# Adafruit_PiTFT_2_4in_HAT.net
KiCad netlist of a schematic drawn in EAGLE
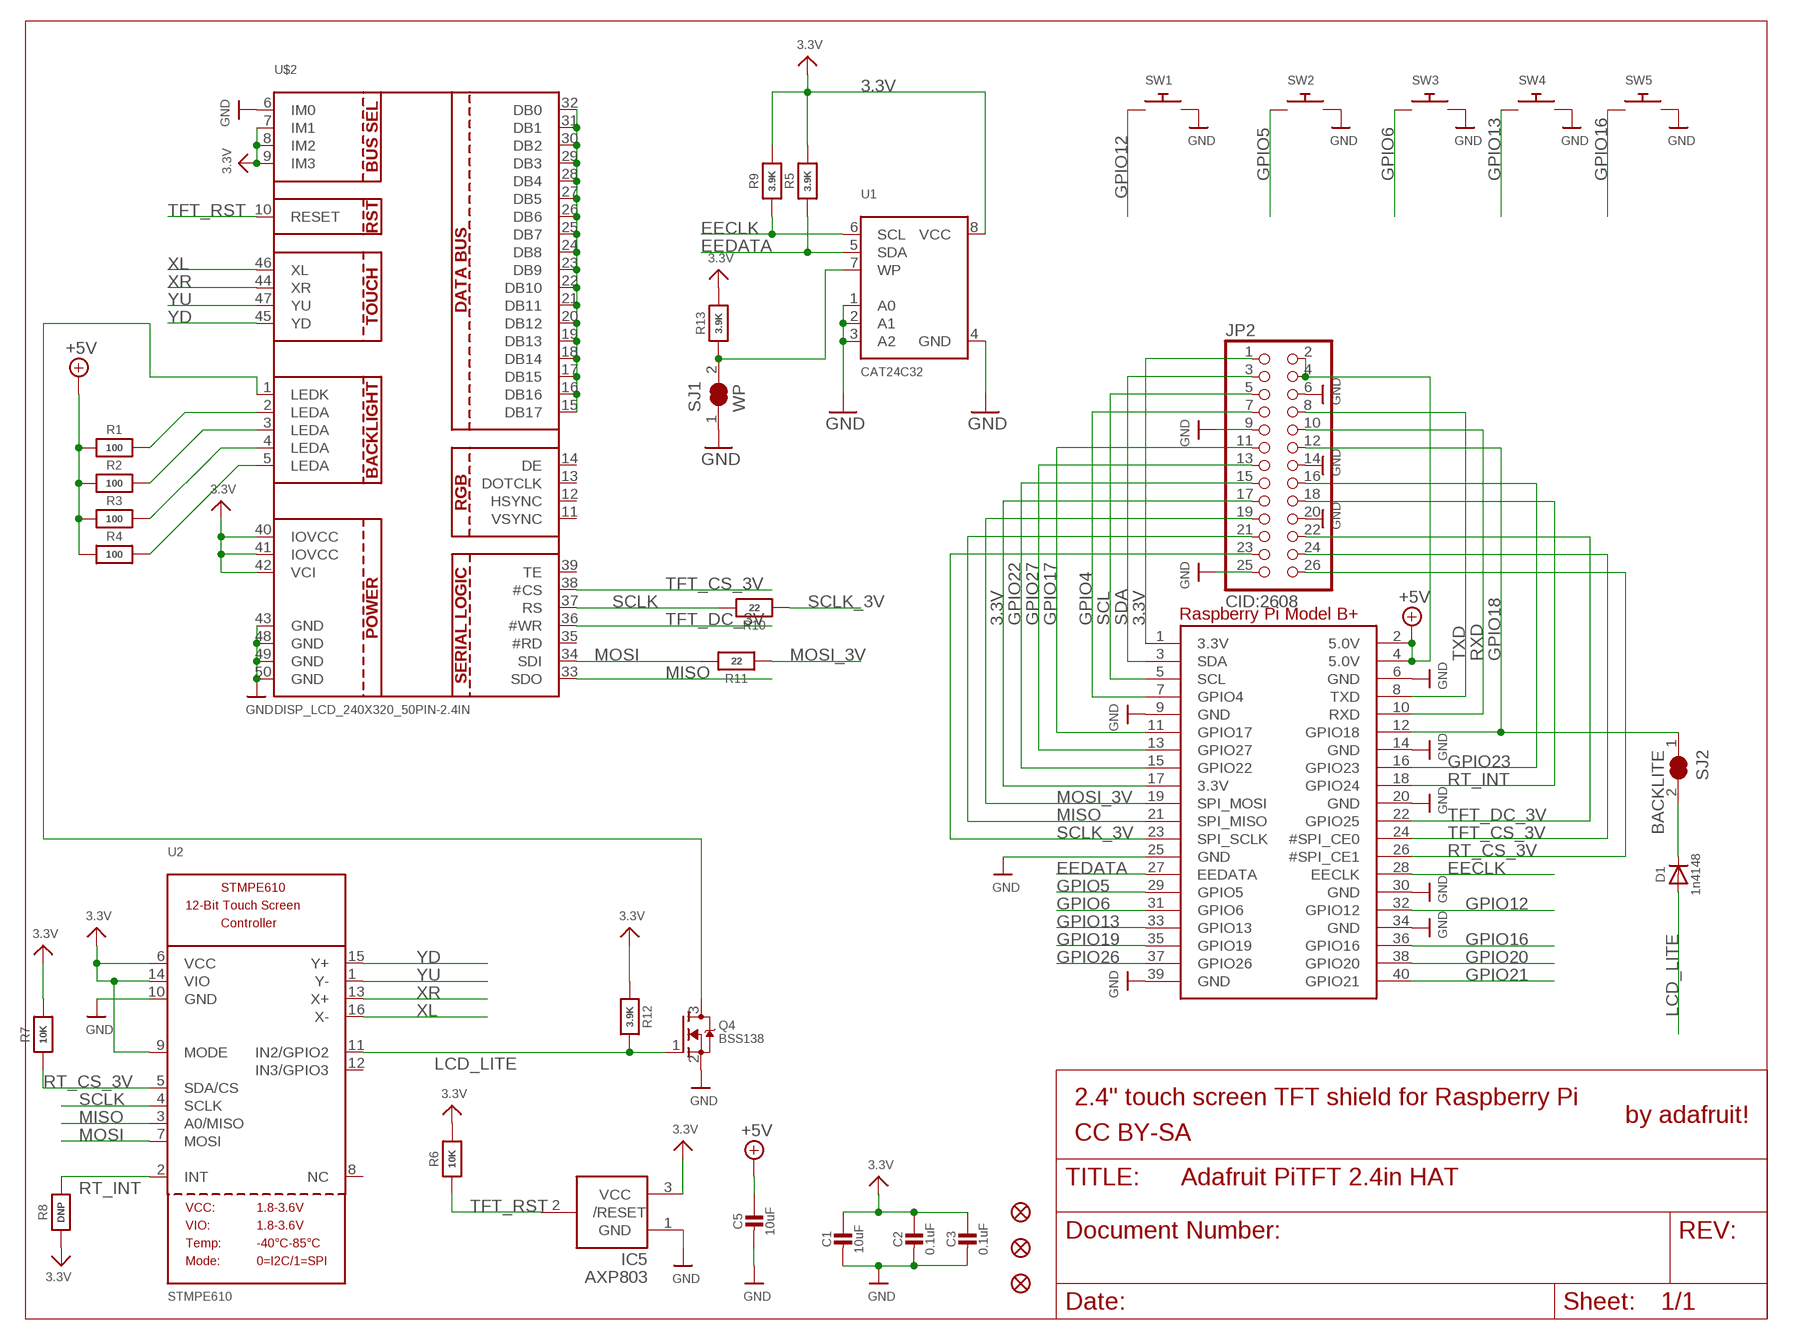
[diagram p0: schematic, sheet 1]

(export (version "E")
  (design (tool "Eeschema 10.0.6"))
  (components
    (comp (ref "C1")
      (value "10uF")
      (footprint "eagle-import:0805-NO")
      (libsource (lib "eagle-import") (part "CAP_CERAMIC0805-NOOUTLINE"))
    )
    (comp (ref "C2")
      (value "0.1uF")
      (footprint "eagle-import:0805-NO")
      (libsource (lib "eagle-import") (part "CAP_CERAMIC0805-NOOUTLINE"))
    )
    (comp (ref "C3")
      (value "0.1uF")
      (footprint "eagle-import:0805-NO")
      (libsource (lib "eagle-import") (part "CAP_CERAMIC0805-NOOUTLINE"))
    )
    (comp (ref "C5")
      (value "10uF")
      (footprint "eagle-import:0805-NO")
      (libsource (lib "eagle-import") (part "CAP_CERAMIC0805-NOOUTLINE"))
    )
    (comp (ref "D1")
      (value "1n4148")
      (footprint "eagle-import:SOD-323")
      (libsource (lib "eagle-import") (part "DIODESOD-323"))
    )
    (comp (ref "IC5")
      (value "AXP803")
      (footprint "eagle-import:SOT23")
      (libsource (lib "eagle-import") (part "AXP083-SAG"))
    )
    (comp (ref "JP2")
      (value "CID:2608")
      (footprint "eagle-import:2X13_SMT_MALE")
      (libsource (lib "eagle-import") (part "HEADER-2X13-SMT"))
    )
    (comp (ref "Q4")
      (value "BSS138")
      (footprint "eagle-import:SOT23-WIDE")
      (libsource (lib "eagle-import") (part "MOSFET-NWIDE"))
    )
    (comp (ref "R1")
      (value "100")
      (footprint "eagle-import:0805-NO")
      (libsource (lib "eagle-import") (part "RESISTOR0805_NOOUTLINE"))
    )
    (comp (ref "R2")
      (value "100")
      (footprint "eagle-import:0805-NO")
      (libsource (lib "eagle-import") (part "RESISTOR0805_NOOUTLINE"))
    )
    (comp (ref "R3")
      (value "100")
      (footprint "eagle-import:0805-NO")
      (libsource (lib "eagle-import") (part "RESISTOR0805_NOOUTLINE"))
    )
    (comp (ref "R4")
      (value "100")
      (footprint "eagle-import:0805-NO")
      (libsource (lib "eagle-import") (part "RESISTOR0805_NOOUTLINE"))
    )
    (comp (ref "R5")
      (value "3.9K")
      (footprint "eagle-import:0805-NO")
      (libsource (lib "eagle-import") (part "RESISTOR0805_NOOUTLINE"))
    )
    (comp (ref "R6")
      (value "10K")
      (footprint "eagle-import:0805-NO")
      (libsource (lib "eagle-import") (part "RESISTOR0805_NOOUTLINE"))
    )
    (comp (ref "R7")
      (value "10K")
      (footprint "eagle-import:0805-NO")
      (libsource (lib "eagle-import") (part "RESISTOR0805_NOOUTLINE"))
    )
    (comp (ref "R8")
      (value "DNP")
      (footprint "eagle-import:0805-NO")
      (libsource (lib "eagle-import") (part "RESISTOR0805_NOOUTLINE"))
    )
    (comp (ref "R9")
      (value "3.9K")
      (footprint "eagle-import:0805-NO")
      (libsource (lib "eagle-import") (part "RESISTOR0805_NOOUTLINE"))
    )
    (comp (ref "R10")
      (value "22")
      (footprint "eagle-import:0805-NO")
      (libsource (lib "eagle-import") (part "RESISTOR0805_NOOUTLINE"))
    )
    (comp (ref "R11")
      (value "22")
      (footprint "eagle-import:0805-NO")
      (libsource (lib "eagle-import") (part "RESISTOR0805_NOOUTLINE"))
    )
    (comp (ref "R12")
      (value "3.9K")
      (footprint "eagle-import:0805-NO")
      (libsource (lib "eagle-import") (part "RESISTOR0805_NOOUTLINE"))
    )
    (comp (ref "R13")
      (value "3.9K")
      (footprint "eagle-import:0805-NO")
      (libsource (lib "eagle-import") (part "RESISTOR0805_NOOUTLINE"))
    )
    (comp (ref "RPI1")
      (value "RASPBERRYPI_BPLUS_HATNOSLOTS")
      (footprint "eagle-import:PI_HAT_NOSLOTS")
      (libsource (lib "eagle-import") (part "RASPBERRYPI_BPLUS_HATNOSLOTS"))
    )
    (comp (ref "SJ1")
      (value "WP")
      (footprint "eagle-import:SOLDERJUMPER_CLOSEDWIRE")
      (libsource (lib "eagle-import") (part "SOLDERJUMPER_CLOSED"))
    )
    (comp (ref "SJ2")
      (value "BACKLITE")
      (footprint "eagle-import:SOLDERJUMPER_CLOSEDWIRE")
      (libsource (lib "eagle-import") (part "SOLDERJUMPER_CLOSED"))
    )
    (comp (ref "SW1")
      (value "SWITCH_PUSHBUTTONEVQ-PE")
      (footprint "eagle-import:TACT_PANA-EVQ")
      (libsource (lib "eagle-import") (part "SWITCH_PUSHBUTTONEVQ-PE"))
    )
    (comp (ref "SW2")
      (value "SWITCH_PUSHBUTTONEVQ-PE")
      (footprint "eagle-import:TACT_PANA-EVQ")
      (libsource (lib "eagle-import") (part "SWITCH_PUSHBUTTONEVQ-PE"))
    )
    (comp (ref "SW3")
      (value "SWITCH_PUSHBUTTONEVQ-PE")
      (footprint "eagle-import:TACT_PANA-EVQ")
      (libsource (lib "eagle-import") (part "SWITCH_PUSHBUTTONEVQ-PE"))
    )
    (comp (ref "SW4")
      (value "SWITCH_PUSHBUTTONEVQ-PE")
      (footprint "eagle-import:TACT_PANA-EVQ")
      (libsource (lib "eagle-import") (part "SWITCH_PUSHBUTTONEVQ-PE"))
    )
    (comp (ref "SW5")
      (value "SWITCH_PUSHBUTTONEVQ-PE")
      (footprint "eagle-import:TACT_PANA-EVQ")
      (libsource (lib "eagle-import") (part "SWITCH_PUSHBUTTONEVQ-PE"))
    )
    (comp (ref "U$2")
      (value "DISP_LCD_240X320_50PIN-2.4IN")
      (footprint "eagle-import:TFT_2.4IN_240X320_50PIN")
      (libsource (lib "eagle-import") (part "DISP_LCD_240X320_50PIN-2.4IN"))
    )
    (comp (ref "U$10")
      (value "FIDUCIAL\"\"")
      (footprint "eagle-import:FIDUCIAL_1MM")
      (libsource (lib "eagle-import") (part "FIDUCIAL{dblquote}{dblquote}"))
    )
    (comp (ref "U$11")
      (value "FIDUCIAL\"\"")
      (footprint "eagle-import:FIDUCIAL_1MM")
      (libsource (lib "eagle-import") (part "FIDUCIAL{dblquote}{dblquote}"))
    )
    (comp (ref "U$18")
      (value "FIDUCIAL\"\"")
      (footprint "eagle-import:FIDUCIAL_1MM")
      (libsource (lib "eagle-import") (part "FIDUCIAL{dblquote}{dblquote}"))
    )
    (comp (ref "U1")
      (value "CAT24C32")
      (footprint "eagle-import:SOIC8_150MIL")
      (libsource (lib "eagle-import") (part "EEPROM_I2C_SOIC8_GENERIC"))
    )
    (comp (ref "U2")
      (value "STMPE610")
      (footprint "eagle-import:QFN16_3MM")
      (libsource (lib "eagle-import") (part "STMPE610"))
    )
  )
  (nets
    (net (code "1") (name "+5V") (class "Default")
      (node (ref "C5") (pin "1") (pinfunction "1_1") (pintype "passive"))
      (node (ref "JP2") (pin "2") (pinfunction "2_2") (pintype "passive"))
      (node (ref "JP2") (pin "4") (pinfunction "4_4") (pintype "passive"))
      (node (ref "R1") (pin "1") (pinfunction "1_1") (pintype "passive"))
      (node (ref "R2") (pin "1") (pinfunction "1_1") (pintype "passive"))
      (node (ref "R3") (pin "1") (pinfunction "1_1") (pintype "passive"))
      (node (ref "R4") (pin "1") (pinfunction "1_1") (pintype "passive"))
      (node (ref "RPI1") (pin "2") (pinfunction "5.0V_2") (pintype "power_in"))
      (node (ref "RPI1") (pin "4") (pinfunction "5.0V_4") (pintype "power_in"))
    )
    (net (code "2") (name "/EECLK") (class "Default")
      (node (ref "R9") (pin "1") (pinfunction "1_1") (pintype "passive"))
      (node (ref "RPI1") (pin "28") (pinfunction "EECLK_28") (pintype "bidirectional"))
      (node (ref "U1") (pin "6") (pinfunction "SCL_6") (pintype "input"))
    )
    (net (code "3") (name "/EEDATA") (class "Default")
      (node (ref "R5") (pin "1") (pinfunction "1_1") (pintype "passive"))
      (node (ref "RPI1") (pin "27") (pinfunction "EEDATA_27") (pintype "bidirectional"))
      (node (ref "U1") (pin "5") (pinfunction "SDA_5") (pintype "bidirectional"))
    )
    (net (code "4") (name "/GPIO4") (class "Default")
      (node (ref "JP2") (pin "7") (pinfunction "7_7") (pintype "passive"))
      (node (ref "RPI1") (pin "7") (pinfunction "GPIO4_7") (pintype "bidirectional"))
    )
    (net (code "5") (name "/GPIO5") (class "Default")
      (node (ref "RPI1") (pin "29") (pinfunction "GPIO5_29") (pintype "bidirectional"))
      (node (ref "SW2") (pin "P$1") (pinfunction "P$1_P$1") (pintype "passive"))
    )
    (net (code "6") (name "/GPIO6") (class "Default")
      (node (ref "RPI1") (pin "31") (pinfunction "GPIO6_31") (pintype "bidirectional"))
      (node (ref "SW3") (pin "P$1") (pinfunction "P$1_P$1") (pintype "passive"))
    )
    (net (code "7") (name "/GPIO12") (class "Default")
      (node (ref "RPI1") (pin "32") (pinfunction "GPIO12_32") (pintype "bidirectional"))
      (node (ref "SW1") (pin "P$1") (pinfunction "P$1_P$1") (pintype "passive"))
    )
    (net (code "8") (name "/GPIO13") (class "Default")
      (node (ref "RPI1") (pin "33") (pinfunction "GPIO13_33") (pintype "bidirectional"))
      (node (ref "SW4") (pin "P$1") (pinfunction "P$1_P$1") (pintype "passive"))
    )
    (net (code "9") (name "/GPIO16") (class "Default")
      (node (ref "RPI1") (pin "36") (pinfunction "GPIO16_36") (pintype "bidirectional"))
      (node (ref "SW5") (pin "P$1") (pinfunction "P$1_P$1") (pintype "passive"))
    )
    (net (code "10") (name "/GPIO17") (class "Default")
      (node (ref "JP2") (pin "11") (pinfunction "11_11") (pintype "passive"))
      (node (ref "RPI1") (pin "11") (pinfunction "GPIO17_11") (pintype "bidirectional"))
    )
    (net (code "11") (name "/GPIO18") (class "Default")
      (node (ref "JP2") (pin "12") (pinfunction "12_12") (pintype "passive"))
      (node (ref "RPI1") (pin "12") (pinfunction "GPIO18_12") (pintype "bidirectional"))
      (node (ref "SJ2") (pin "1") (pinfunction "1_1") (pintype "passive"))
    )
    (net (code "12") (name "/GPIO19") (class "Default")
      (node (ref "RPI1") (pin "35") (pinfunction "GPIO19_35") (pintype "bidirectional"))
    )
    (net (code "13") (name "/GPIO20") (class "Default")
      (node (ref "RPI1") (pin "38") (pinfunction "GPIO20_38") (pintype "bidirectional"))
    )
    (net (code "14") (name "/GPIO21") (class "Default")
      (node (ref "RPI1") (pin "40") (pinfunction "GPIO21_40") (pintype "bidirectional"))
    )
    (net (code "15") (name "/GPIO22") (class "Default")
      (node (ref "JP2") (pin "15") (pinfunction "15_15") (pintype "passive"))
      (node (ref "RPI1") (pin "15") (pinfunction "GPIO22_15") (pintype "bidirectional"))
    )
    (net (code "16") (name "/GPIO23") (class "Default")
      (node (ref "JP2") (pin "16") (pinfunction "16_16") (pintype "passive"))
      (node (ref "RPI1") (pin "16") (pinfunction "GPIO23_16") (pintype "bidirectional"))
    )
    (net (code "17") (name "/GPIO26") (class "Default")
      (node (ref "RPI1") (pin "37") (pinfunction "GPIO26_37") (pintype "bidirectional"))
    )
    (net (code "18") (name "/GPIO27") (class "Default")
      (node (ref "JP2") (pin "13") (pinfunction "13_13") (pintype "passive"))
      (node (ref "RPI1") (pin "13") (pinfunction "GPIO27_13") (pintype "bidirectional"))
    )
    (net (code "19") (name "/LCD_LITE") (class "Default")
      (node (ref "D1") (pin "A") (pinfunction "A_A") (pintype "passive"))
      (node (ref "Q4") (pin "1") (pinfunction "G_1") (pintype "bidirectional"))
      (node (ref "R12") (pin "2") (pinfunction "2_2") (pintype "passive"))
      (node (ref "U2") (pin "11") (pinfunction "IN2/GPIO2_11") (pintype "bidirectional"))
    )
    (net (code "20") (name "/MISO") (class "Default")
      (node (ref "JP2") (pin "21") (pinfunction "21_21") (pintype "passive"))
      (node (ref "RPI1") (pin "21") (pinfunction "SPI_MISO_21") (pintype "bidirectional"))
      (node (ref "U$2") (pin "33") (pinfunction "SDO_33") (pintype "bidirectional"))
      (node (ref "U2") (pin "3") (pinfunction "A0/MISO_3") (pintype "bidirectional"))
    )
    (net (code "21") (name "/MOSI") (class "Default")
      (node (ref "R11") (pin "2") (pinfunction "2_2") (pintype "passive"))
      (node (ref "U$2") (pin "34") (pinfunction "SDI_34") (pintype "bidirectional"))
      (node (ref "U2") (pin "7") (pinfunction "MOSI_7") (pintype "input"))
    )
    (net (code "22") (name "/MOSI_3V") (class "Default")
      (node (ref "JP2") (pin "19") (pinfunction "19_19") (pintype "passive"))
      (node (ref "R11") (pin "1") (pinfunction "1_1") (pintype "passive"))
      (node (ref "RPI1") (pin "19") (pinfunction "SPI_MOSI_19") (pintype "bidirectional"))
    )
    (net (code "23") (name "/RT_CS_3V") (class "Default")
      (node (ref "JP2") (pin "26") (pinfunction "26_26") (pintype "passive"))
      (node (ref "R7") (pin "1") (pinfunction "1_1") (pintype "passive"))
      (node (ref "RPI1") (pin "26") (pinfunction "#SPI_CE1_26") (pintype "bidirectional"))
      (node (ref "U2") (pin "5") (pinfunction "SDA/CS_5") (pintype "bidirectional"))
    )
    (net (code "24") (name "/RT_INT") (class "Default")
      (node (ref "JP2") (pin "18") (pinfunction "18_18") (pintype "passive"))
      (node (ref "R8") (pin "2") (pinfunction "2_2") (pintype "passive"))
      (node (ref "RPI1") (pin "18") (pinfunction "GPIO24_18") (pintype "bidirectional"))
      (node (ref "U2") (pin "2") (pinfunction "INT_2") (pintype "output"))
    )
    (net (code "25") (name "/RXD") (class "Default")
      (node (ref "JP2") (pin "10") (pinfunction "10_10") (pintype "passive"))
      (node (ref "RPI1") (pin "10") (pinfunction "RXD_10") (pintype "bidirectional"))
    )
    (net (code "26") (name "/SCL") (class "Default")
      (node (ref "JP2") (pin "5") (pinfunction "5_5") (pintype "passive"))
      (node (ref "RPI1") (pin "5") (pinfunction "SCL_5") (pintype "bidirectional"))
    )
    (net (code "27") (name "/SCLK") (class "Default")
      (node (ref "R10") (pin "2") (pinfunction "2_2") (pintype "passive"))
      (node (ref "U$2") (pin "37") (pinfunction "RS_37") (pintype "bidirectional"))
      (node (ref "U2") (pin "4") (pinfunction "SCLK_4") (pintype "bidirectional"))
    )
    (net (code "28") (name "/SCLK_3V") (class "Default")
      (node (ref "JP2") (pin "23") (pinfunction "23_23") (pintype "passive"))
      (node (ref "R10") (pin "1") (pinfunction "1_1") (pintype "passive"))
      (node (ref "RPI1") (pin "23") (pinfunction "SPI_SCLK_23") (pintype "bidirectional"))
    )
    (net (code "29") (name "/SDA") (class "Default")
      (node (ref "JP2") (pin "3") (pinfunction "3_3") (pintype "passive"))
      (node (ref "RPI1") (pin "3") (pinfunction "SDA_3") (pintype "bidirectional"))
    )
    (net (code "30") (name "/TFT_CS_3V") (class "Default")
      (node (ref "JP2") (pin "24") (pinfunction "24_24") (pintype "passive"))
      (node (ref "RPI1") (pin "24") (pinfunction "#SPI_CE0_24") (pintype "bidirectional"))
      (node (ref "U$2") (pin "38") (pinfunction "#CS_38") (pintype "bidirectional"))
    )
    (net (code "31") (name "/TFT_DC_3V") (class "Default")
      (node (ref "JP2") (pin "22") (pinfunction "22_22") (pintype "passive"))
      (node (ref "RPI1") (pin "22") (pinfunction "GPIO25_22") (pintype "bidirectional"))
      (node (ref "U$2") (pin "36") (pinfunction "#WR_36") (pintype "bidirectional"))
    )
    (net (code "32") (name "/TFT_RST") (class "Default")
      (node (ref "IC5") (pin "2") (pinfunction "/RESET_2") (pintype "output"))
      (node (ref "R6") (pin "1") (pinfunction "1_1") (pintype "passive"))
      (node (ref "U$2") (pin "10") (pinfunction "RESET_10") (pintype "bidirectional"))
    )
    (net (code "33") (name "/TXD") (class "Default")
      (node (ref "JP2") (pin "8") (pinfunction "8_8") (pintype "passive"))
      (node (ref "RPI1") (pin "8") (pinfunction "TXD_8") (pintype "bidirectional"))
    )
    (net (code "34") (name "/XL") (class "Default")
      (node (ref "U$2") (pin "46") (pinfunction "XL_46") (pintype "bidirectional"))
      (node (ref "U2") (pin "16") (pinfunction "X-_16") (pintype "input"))
    )
    (net (code "35") (name "/XR") (class "Default")
      (node (ref "U$2") (pin "44") (pinfunction "XR_44") (pintype "bidirectional"))
      (node (ref "U2") (pin "13") (pinfunction "X+_13") (pintype "input"))
    )
    (net (code "36") (name "/YD") (class "Default")
      (node (ref "U$2") (pin "45") (pinfunction "YD_45") (pintype "bidirectional"))
      (node (ref "U2") (pin "15") (pinfunction "Y+_15") (pintype "input"))
    )
    (net (code "37") (name "/YU") (class "Default")
      (node (ref "U$2") (pin "47") (pinfunction "YU_47") (pintype "bidirectional"))
      (node (ref "U2") (pin "1") (pinfunction "Y-_1") (pintype "input"))
    )
    (net (code "38") (name "3.3V") (class "Default")
      (node (ref "C1") (pin "1") (pinfunction "1_1") (pintype "passive"))
      (node (ref "C2") (pin "1") (pinfunction "1_1") (pintype "passive"))
      (node (ref "C3") (pin "1") (pinfunction "1_1") (pintype "passive"))
      (node (ref "IC5") (pin "3") (pinfunction "VCC_3") (pintype "power_in"))
      (node (ref "JP2") (pin "1") (pinfunction "1_1") (pintype "passive"))
      (node (ref "JP2") (pin "17") (pinfunction "17_17") (pintype "passive"))
      (node (ref "R12") (pin "1") (pinfunction "1_1") (pintype "passive"))
      (node (ref "R13") (pin "2") (pinfunction "2_2") (pintype "passive"))
      (node (ref "R5") (pin "2") (pinfunction "2_2") (pintype "passive"))
      (node (ref "R6") (pin "2") (pinfunction "2_2") (pintype "passive"))
      (node (ref "R7") (pin "2") (pinfunction "2_2") (pintype "passive"))
      (node (ref "R8") (pin "1") (pinfunction "1_1") (pintype "passive"))
      (node (ref "R9") (pin "2") (pinfunction "2_2") (pintype "passive"))
      (node (ref "RPI1") (pin "1") (pinfunction "3.3V_1") (pintype "power_in"))
      (node (ref "RPI1") (pin "17") (pinfunction "3.3V_17") (pintype "power_in"))
      (node (ref "U$2") (pin "40") (pinfunction "IOVCC_40") (pintype "bidirectional"))
      (node (ref "U$2") (pin "41") (pinfunction "IOVCC_41") (pintype "bidirectional"))
      (node (ref "U$2") (pin "42") (pinfunction "VCI_42") (pintype "bidirectional"))
      (node (ref "U$2") (pin "7") (pinfunction "IM1_7") (pintype "bidirectional"))
      (node (ref "U$2") (pin "8") (pinfunction "IM2_8") (pintype "bidirectional"))
      (node (ref "U$2") (pin "9") (pinfunction "IM3_9") (pintype "bidirectional"))
      (node (ref "U1") (pin "8") (pinfunction "VCC_8") (pintype "power_in"))
      (node (ref "U2") (pin "14") (pinfunction "VIO_14") (pintype "power_in"))
      (node (ref "U2") (pin "6") (pinfunction "VCC_6") (pintype "power_in"))
      (node (ref "U2") (pin "9") (pinfunction "MODE_9") (pintype "input"))
    )
    (net (code "39") (name "GND") (class "Default")
      (node (ref "C1") (pin "2") (pinfunction "2_2") (pintype "passive"))
      (node (ref "C2") (pin "2") (pinfunction "2_2") (pintype "passive"))
      (node (ref "C3") (pin "2") (pinfunction "2_2") (pintype "passive"))
      (node (ref "C5") (pin "2") (pinfunction "2_2") (pintype "passive"))
      (node (ref "IC5") (pin "1") (pinfunction "GND_1") (pintype "power_in"))
      (node (ref "JP2") (pin "14") (pinfunction "14_14") (pintype "passive"))
      (node (ref "JP2") (pin "20") (pinfunction "20_20") (pintype "passive"))
      (node (ref "JP2") (pin "25") (pinfunction "25_25") (pintype "passive"))
      (node (ref "JP2") (pin "6") (pinfunction "6_6") (pintype "passive"))
      (node (ref "JP2") (pin "9") (pinfunction "9_9") (pintype "passive"))
      (node (ref "Q4") (pin "2") (pinfunction "S_2") (pintype "bidirectional"))
      (node (ref "RPI1") (pin "14") (pinfunction "GND_14") (pintype "power_in"))
      (node (ref "RPI1") (pin "20") (pinfunction "GND_20") (pintype "power_in"))
      (node (ref "RPI1") (pin "25") (pinfunction "GND_25") (pintype "power_in"))
      (node (ref "RPI1") (pin "30") (pinfunction "GND_30") (pintype "power_in"))
      (node (ref "RPI1") (pin "34") (pinfunction "GND_34") (pintype "power_in"))
      (node (ref "RPI1") (pin "39") (pinfunction "GND_39") (pintype "power_in"))
      (node (ref "RPI1") (pin "6") (pinfunction "GND_6") (pintype "power_in"))
      (node (ref "RPI1") (pin "9") (pinfunction "GND_9") (pintype "power_in"))
      (node (ref "SJ1") (pin "1") (pinfunction "1_1") (pintype "passive"))
      (node (ref "SW1") (pin "P$2") (pinfunction "P$2_P$2") (pintype "passive"))
      (node (ref "SW2") (pin "P$2") (pinfunction "P$2_P$2") (pintype "passive"))
      (node (ref "SW3") (pin "P$2") (pinfunction "P$2_P$2") (pintype "passive"))
      (node (ref "SW4") (pin "P$2") (pinfunction "P$2_P$2") (pintype "passive"))
      (node (ref "SW5") (pin "P$2") (pinfunction "P$2_P$2") (pintype "passive"))
      (node (ref "U$2") (pin "43") (pinfunction "GND_43") (pintype "bidirectional"))
      (node (ref "U$2") (pin "48") (pinfunction "GND_48") (pintype "bidirectional"))
      (node (ref "U$2") (pin "49") (pinfunction "GND_49") (pintype "bidirectional"))
      (node (ref "U$2") (pin "50") (pinfunction "GND_50") (pintype "bidirectional"))
      (node (ref "U$2") (pin "6") (pinfunction "IM0_6") (pintype "bidirectional"))
      (node (ref "U1") (pin "1") (pinfunction "A0_1") (pintype "input"))
      (node (ref "U1") (pin "2") (pinfunction "A1_2") (pintype "input"))
      (node (ref "U1") (pin "3") (pinfunction "A2_3") (pintype "input"))
      (node (ref "U1") (pin "4") (pinfunction "GND_4") (pintype "power_in"))
      (node (ref "U2") (pin "10") (pinfunction "GND_10") (pintype "power_in"))
    )
    (net (code "40") (name "Net-(D1-PadC)") (class "Default")
      (node (ref "D1") (pin "C") (pinfunction "C_C") (pintype "passive"))
      (node (ref "SJ2") (pin "2") (pinfunction "2_2") (pintype "passive"))
    )
    (net (code "41") (name "Net-(Q4-D)") (class "Default")
      (node (ref "Q4") (pin "3") (pinfunction "D_3") (pintype "bidirectional"))
      (node (ref "U$2") (pin "1") (pinfunction "LEDK_1") (pintype "bidirectional"))
    )
    (net (code "42") (name "Net-(R1-Pad2)") (class "Default")
      (node (ref "R1") (pin "2") (pinfunction "2_2") (pintype "passive"))
      (node (ref "U$2") (pin "2") (pinfunction "LEDA_2") (pintype "bidirectional"))
    )
    (net (code "43") (name "Net-(R2-Pad2)") (class "Default")
      (node (ref "R2") (pin "2") (pinfunction "2_2") (pintype "passive"))
      (node (ref "U$2") (pin "3") (pinfunction "LEDA_3") (pintype "bidirectional"))
    )
    (net (code "44") (name "Net-(R3-Pad2)") (class "Default")
      (node (ref "R3") (pin "2") (pinfunction "2_2") (pintype "passive"))
      (node (ref "U$2") (pin "4") (pinfunction "LEDA_4") (pintype "bidirectional"))
    )
    (net (code "45") (name "Net-(R4-Pad2)") (class "Default")
      (node (ref "R4") (pin "2") (pinfunction "2_2") (pintype "passive"))
      (node (ref "U$2") (pin "5") (pinfunction "LEDA_5") (pintype "bidirectional"))
    )
    (net (code "46") (name "Net-(U$2-DB0)") (class "Default")
      (node (ref "U$2") (pin "15") (pinfunction "DB17_15") (pintype "bidirectional"))
      (node (ref "U$2") (pin "16") (pinfunction "DB16_16") (pintype "bidirectional"))
      (node (ref "U$2") (pin "17") (pinfunction "DB15_17") (pintype "bidirectional"))
      (node (ref "U$2") (pin "18") (pinfunction "DB14_18") (pintype "bidirectional"))
      (node (ref "U$2") (pin "19") (pinfunction "DB13_19") (pintype "bidirectional"))
      (node (ref "U$2") (pin "20") (pinfunction "DB12_20") (pintype "bidirectional"))
      (node (ref "U$2") (pin "21") (pinfunction "DB11_21") (pintype "bidirectional"))
      (node (ref "U$2") (pin "22") (pinfunction "DB10_22") (pintype "bidirectional"))
      (node (ref "U$2") (pin "23") (pinfunction "DB9_23") (pintype "bidirectional"))
      (node (ref "U$2") (pin "24") (pinfunction "DB8_24") (pintype "bidirectional"))
      (node (ref "U$2") (pin "25") (pinfunction "DB7_25") (pintype "bidirectional"))
      (node (ref "U$2") (pin "26") (pinfunction "DB6_26") (pintype "bidirectional"))
      (node (ref "U$2") (pin "27") (pinfunction "DB5_27") (pintype "bidirectional"))
      (node (ref "U$2") (pin "28") (pinfunction "DB4_28") (pintype "bidirectional"))
      (node (ref "U$2") (pin "29") (pinfunction "DB3_29") (pintype "bidirectional"))
      (node (ref "U$2") (pin "30") (pinfunction "DB2_30") (pintype "bidirectional"))
      (node (ref "U$2") (pin "31") (pinfunction "DB1_31") (pintype "bidirectional"))
      (node (ref "U$2") (pin "32") (pinfunction "DB0_32") (pintype "bidirectional"))
    )
    (net (code "47") (name "Net-(U1-WP)") (class "Default")
      (node (ref "R13") (pin "1") (pinfunction "1_1") (pintype "passive"))
      (node (ref "SJ1") (pin "2") (pinfunction "2_2") (pintype "passive"))
      (node (ref "U1") (pin "7") (pinfunction "WP_7") (pintype "input"))
    )
    (net (code "48") (name "unconnected-(U$2-#RD-Pad35)") (class "Default")
      (node (ref "U$2") (pin "35") (pinfunction "#RD_35") (pintype "bidirectional"))
    )
    (net (code "49") (name "unconnected-(U$2-DE-Pad14)") (class "Default")
      (node (ref "U$2") (pin "14") (pinfunction "DE_14") (pintype "bidirectional"))
    )
    (net (code "50") (name "unconnected-(U$2-DOTCLK-Pad13)") (class "Default")
      (node (ref "U$2") (pin "13") (pinfunction "DOTCLK_13") (pintype "bidirectional"))
    )
    (net (code "51") (name "unconnected-(U$2-HSYNC-Pad12)") (class "Default")
      (node (ref "U$2") (pin "12") (pinfunction "HSYNC_12") (pintype "bidirectional"))
    )
    (net (code "52") (name "unconnected-(U$2-TE-Pad39)") (class "Default")
      (node (ref "U$2") (pin "39") (pinfunction "TE_39") (pintype "bidirectional"))
    )
    (net (code "53") (name "unconnected-(U$2-VSYNC-Pad11)") (class "Default")
      (node (ref "U$2") (pin "11") (pinfunction "VSYNC_11") (pintype "bidirectional"))
    )
    (net (code "54") (name "unconnected-(U2-IN3{slash}GPIO3-Pad12)") (class "Default")
      (node (ref "U2") (pin "12") (pinfunction "IN3/GPIO3_12") (pintype "bidirectional"))
    )
    (net (code "55") (name "unconnected-(U2-NC-Pad8)") (class "Default")
      (node (ref "U2") (pin "8") (pinfunction "NC_8") (pintype "no_connect"))
    )
  )
)
